# videoReleaseMech.net
KiCad netlist of a schematic drawn in EAGLE
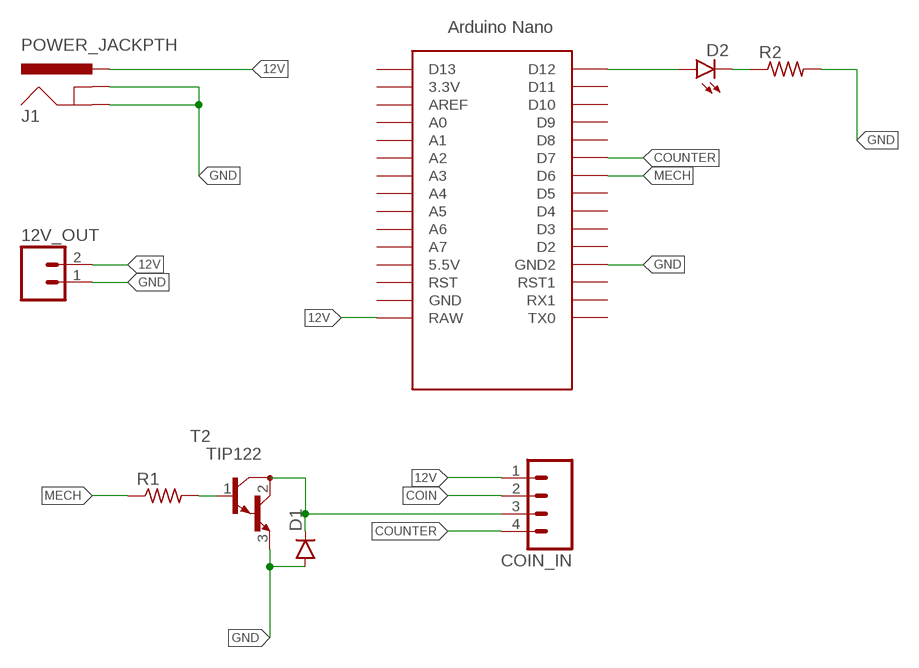
[diagram p0: schematic, sheet 1]

(export (version "E")
  (design (tool "Eeschema 10.0.6"))
  (components
    (comp (ref "12V_OUT")
      (value "M02LOCK_LONGPADS")
      (footprint "eagle-import:1X02_LOCK_LONGPADS")
      (libsource (lib "eagle-import") (part "M02LOCK_LONGPADS"))
    )
    (comp (ref "COIN_IN")
      (value "M041X04_NO_SILK")
      (footprint "eagle-import:1X04_NO_SILK")
      (libsource (lib "eagle-import") (part "M041X04_NO_SILK"))
    )
    (comp (ref "D1")
      (value "DIODEPTH")
      (footprint "eagle-import:DIODE-1N4001")
      (libsource (lib "eagle-import") (part "DIODEPTH"))
    )
    (comp (ref "D2")
      (value "LED5MM")
      (footprint "eagle-import:LED5MM")
      (libsource (lib "eagle-import") (part "LED5MM"))
    )
    (comp (ref "J1")
      (value "POWER_JACKPTH")
      (footprint "eagle-import:POWER_JACK_PTH")
      (libsource (lib "eagle-import") (part "POWER_JACKPTH"))
    )
    (comp (ref "R1")
      (value "R-US_0411/3V")
      (footprint "eagle-import:0411V")
      (libsource (lib "eagle-import") (part "R-US_0411/3V"))
    )
    (comp (ref "R2")
      (value "R-US_0411/3V")
      (footprint "eagle-import:0411V")
      (libsource (lib "eagle-import") (part "R-US_0411/3V"))
    )
    (comp (ref "T2")
      (value "TIP122")
      (footprint "eagle-import:TO220")
      (libsource (lib "eagle-import") (part "TIP122"))
    )
    (comp (ref "U$1")
      (value "NANO")
      (footprint "eagle-import:NANO")
      (libsource (lib "eagle-import") (part "NANO"))
    )
  )
  (nets
    (net (code "1") (name "12V") (class "Default")
      (node (ref "12V_OUT") (pin "2") (pinfunction "2_2") (pintype "passive"))
      (node (ref "COIN_IN") (pin "1") (pinfunction "1_1") (pintype "passive"))
      (node (ref "J1") (pin "PWR") (pinfunction "PWR_PWR") (pintype "bidirectional"))
      (node (ref "U$1") (pin "RAW") (pinfunction "RAW_RAW") (pintype "bidirectional"))
    )
    (net (code "2") (name "COIN") (class "Default")
      (node (ref "COIN_IN") (pin "2") (pinfunction "2_2") (pintype "passive"))
    )
    (net (code "3") (name "COUNTER") (class "Default")
      (node (ref "COIN_IN") (pin "4") (pinfunction "4_4") (pintype "passive"))
      (node (ref "U$1") (pin "D7") (pinfunction "D7_D7") (pintype "bidirectional"))
    )
    (net (code "4") (name "GND") (class "Default")
      (node (ref "12V_OUT") (pin "1") (pinfunction "1_1") (pintype "passive"))
      (node (ref "D1") (pin "A") (pinfunction "A_A") (pintype "passive"))
      (node (ref "J1") (pin "GND") (pinfunction "GND_GND") (pintype "bidirectional"))
      (node (ref "J1") (pin "GNDBREAK") (pinfunction "GNDBREAK_GNDBREAK") (pintype "bidirectional"))
      (node (ref "R2") (pin "2") (pinfunction "2_2") (pintype "passive"))
      (node (ref "T2") (pin "3") (pinfunction "E_3") (pintype "passive"))
      (node (ref "U$1") (pin "GND1") (pinfunction "GND2_GND1") (pintype "bidirectional"))
    )
    (net (code "5") (name "MECH") (class "Default")
      (node (ref "R1") (pin "1") (pinfunction "1_1") (pintype "passive"))
      (node (ref "U$1") (pin "D6") (pinfunction "D6_D6") (pintype "bidirectional"))
    )
    (net (code "6") (name "Net-(D2-C)") (class "Default")
      (node (ref "D2") (pin "K") (pinfunction "C_K") (pintype "passive"))
      (node (ref "R2") (pin "1") (pinfunction "1_1") (pintype "passive"))
    )
    (net (code "7") (name "Net-(D2-PadA)") (class "Default")
      (node (ref "D2") (pin "A") (pinfunction "A_A") (pintype "passive"))
      (node (ref "U$1") (pin "D12") (pinfunction "D12_D12") (pintype "bidirectional"))
    )
    (net (code "8") (name "Net-(T2-B)") (class "Default")
      (node (ref "R1") (pin "2") (pinfunction "2_2") (pintype "passive"))
      (node (ref "T2") (pin "1") (pinfunction "B_1") (pintype "passive"))
    )
    (net (code "9") (name "Net-(T2-C)") (class "Default")
      (node (ref "COIN_IN") (pin "3") (pinfunction "3_3") (pintype "passive"))
      (node (ref "D1") (pin "C") (pinfunction "C_C") (pintype "passive"))
      (node (ref "T2") (pin "2") (pinfunction "C_2") (pintype "passive"))
    )
    (net (code "10") (name "unconnected-(U$1-5.5V-Pad5V)") (class "Default")
      (node (ref "U$1") (pin "5V") (pinfunction "5.5V_5V") (pintype "bidirectional"))
    )
    (net (code "11") (name "unconnected-(U$1-Pad3.3V)") (class "Default")
      (node (ref "U$1") (pin "3.3V") (pinfunction "3.3V_3.3V") (pintype "bidirectional"))
    )
    (net (code "12") (name "unconnected-(U$1-PadA0)") (class "Default")
      (node (ref "U$1") (pin "A0") (pinfunction "A0_A0") (pintype "bidirectional"))
    )
    (net (code "13") (name "unconnected-(U$1-PadA1)") (class "Default")
      (node (ref "U$1") (pin "A1") (pinfunction "A1_A1") (pintype "bidirectional"))
    )
    (net (code "14") (name "unconnected-(U$1-PadA2)") (class "Default")
      (node (ref "U$1") (pin "A2") (pinfunction "A2_A2") (pintype "bidirectional"))
    )
    (net (code "15") (name "unconnected-(U$1-PadA3)") (class "Default")
      (node (ref "U$1") (pin "A3") (pinfunction "A3_A3") (pintype "bidirectional"))
    )
    (net (code "16") (name "unconnected-(U$1-PadA4)") (class "Default")
      (node (ref "U$1") (pin "A4") (pinfunction "A4_A4") (pintype "bidirectional"))
    )
    (net (code "17") (name "unconnected-(U$1-PadA5)") (class "Default")
      (node (ref "U$1") (pin "A5") (pinfunction "A5_A5") (pintype "bidirectional"))
    )
    (net (code "18") (name "unconnected-(U$1-PadA6)") (class "Default")
      (node (ref "U$1") (pin "A6") (pinfunction "A6_A6") (pintype "bidirectional"))
    )
    (net (code "19") (name "unconnected-(U$1-PadA7)") (class "Default")
      (node (ref "U$1") (pin "A7") (pinfunction "A7_A7") (pintype "bidirectional"))
    )
    (net (code "20") (name "unconnected-(U$1-PadAREF)") (class "Default")
      (node (ref "U$1") (pin "AREF") (pinfunction "AREF_AREF") (pintype "bidirectional"))
    )
    (net (code "21") (name "unconnected-(U$1-PadD2)") (class "Default")
      (node (ref "U$1") (pin "D2") (pinfunction "D2_D2") (pintype "bidirectional"))
    )
    (net (code "22") (name "unconnected-(U$1-PadD3)") (class "Default")
      (node (ref "U$1") (pin "D3") (pinfunction "D3_D3") (pintype "bidirectional"))
    )
    (net (code "23") (name "unconnected-(U$1-PadD4)") (class "Default")
      (node (ref "U$1") (pin "D4") (pinfunction "D4_D4") (pintype "bidirectional"))
    )
    (net (code "24") (name "unconnected-(U$1-PadD5)") (class "Default")
      (node (ref "U$1") (pin "D5") (pinfunction "D5_D5") (pintype "bidirectional"))
    )
    (net (code "25") (name "unconnected-(U$1-PadD8)") (class "Default")
      (node (ref "U$1") (pin "D8") (pinfunction "D8_D8") (pintype "bidirectional"))
    )
    (net (code "26") (name "unconnected-(U$1-PadD9)") (class "Default")
      (node (ref "U$1") (pin "D9") (pinfunction "D9_D9") (pintype "bidirectional"))
    )
    (net (code "27") (name "unconnected-(U$1-PadD10)") (class "Default")
      (node (ref "U$1") (pin "D10") (pinfunction "D10_D10") (pintype "bidirectional"))
    )
    (net (code "28") (name "unconnected-(U$1-PadD11)") (class "Default")
      (node (ref "U$1") (pin "D11") (pinfunction "D11_D11") (pintype "bidirectional"))
    )
    (net (code "29") (name "unconnected-(U$1-PadD13)") (class "Default")
      (node (ref "U$1") (pin "D13") (pinfunction "D13_D13") (pintype "bidirectional"))
    )
    (net (code "30") (name "unconnected-(U$1-PadGND)") (class "Default")
      (node (ref "U$1") (pin "GND") (pinfunction "GND_GND") (pintype "bidirectional"))
    )
    (net (code "31") (name "unconnected-(U$1-PadICSP1)") (class "Default")
      (node (ref "U$1") (pin "ICSP1") (pinfunction "ICSP1_ICSP1") (pintype "bidirectional"))
    )
    (net (code "32") (name "unconnected-(U$1-PadICSP2)") (class "Default")
      (node (ref "U$1") (pin "ICSP2") (pinfunction "ICSP2_ICSP2") (pintype "bidirectional"))
    )
    (net (code "33") (name "unconnected-(U$1-PadICSP3)") (class "Default")
      (node (ref "U$1") (pin "ICSP3") (pinfunction "ICSP3_ICSP3") (pintype "bidirectional"))
    )
    (net (code "34") (name "unconnected-(U$1-PadICSP4)") (class "Default")
      (node (ref "U$1") (pin "ICSP4") (pinfunction "ICSP4_ICSP4") (pintype "bidirectional"))
    )
    (net (code "35") (name "unconnected-(U$1-PadICSP5)") (class "Default")
      (node (ref "U$1") (pin "ICSP5") (pinfunction "ICSP5_ICSP5") (pintype "bidirectional"))
    )
    (net (code "36") (name "unconnected-(U$1-PadICSP6)") (class "Default")
      (node (ref "U$1") (pin "ICSP6") (pinfunction "ICSP6_ICSP6") (pintype "bidirectional"))
    )
    (net (code "37") (name "unconnected-(U$1-PadRST)") (class "Default")
      (node (ref "U$1") (pin "RST") (pinfunction "RST_RST") (pintype "bidirectional"))
    )
    (net (code "38") (name "unconnected-(U$1-PadRST1)") (class "Default")
      (node (ref "U$1") (pin "RST1") (pinfunction "RST1_RST1") (pintype "bidirectional"))
    )
    (net (code "39") (name "unconnected-(U$1-PadRX1)") (class "Default")
      (node (ref "U$1") (pin "RX1") (pinfunction "RX1_RX1") (pintype "bidirectional"))
    )
    (net (code "40") (name "unconnected-(U$1-PadTX0)") (class "Default")
      (node (ref "U$1") (pin "TX0") (pinfunction "TX0_TX0") (pintype "bidirectional"))
    )
  )
)
